# G850V_ESP8266_II_v6.net
KiCad netlist of a schematic drawn in EAGLE
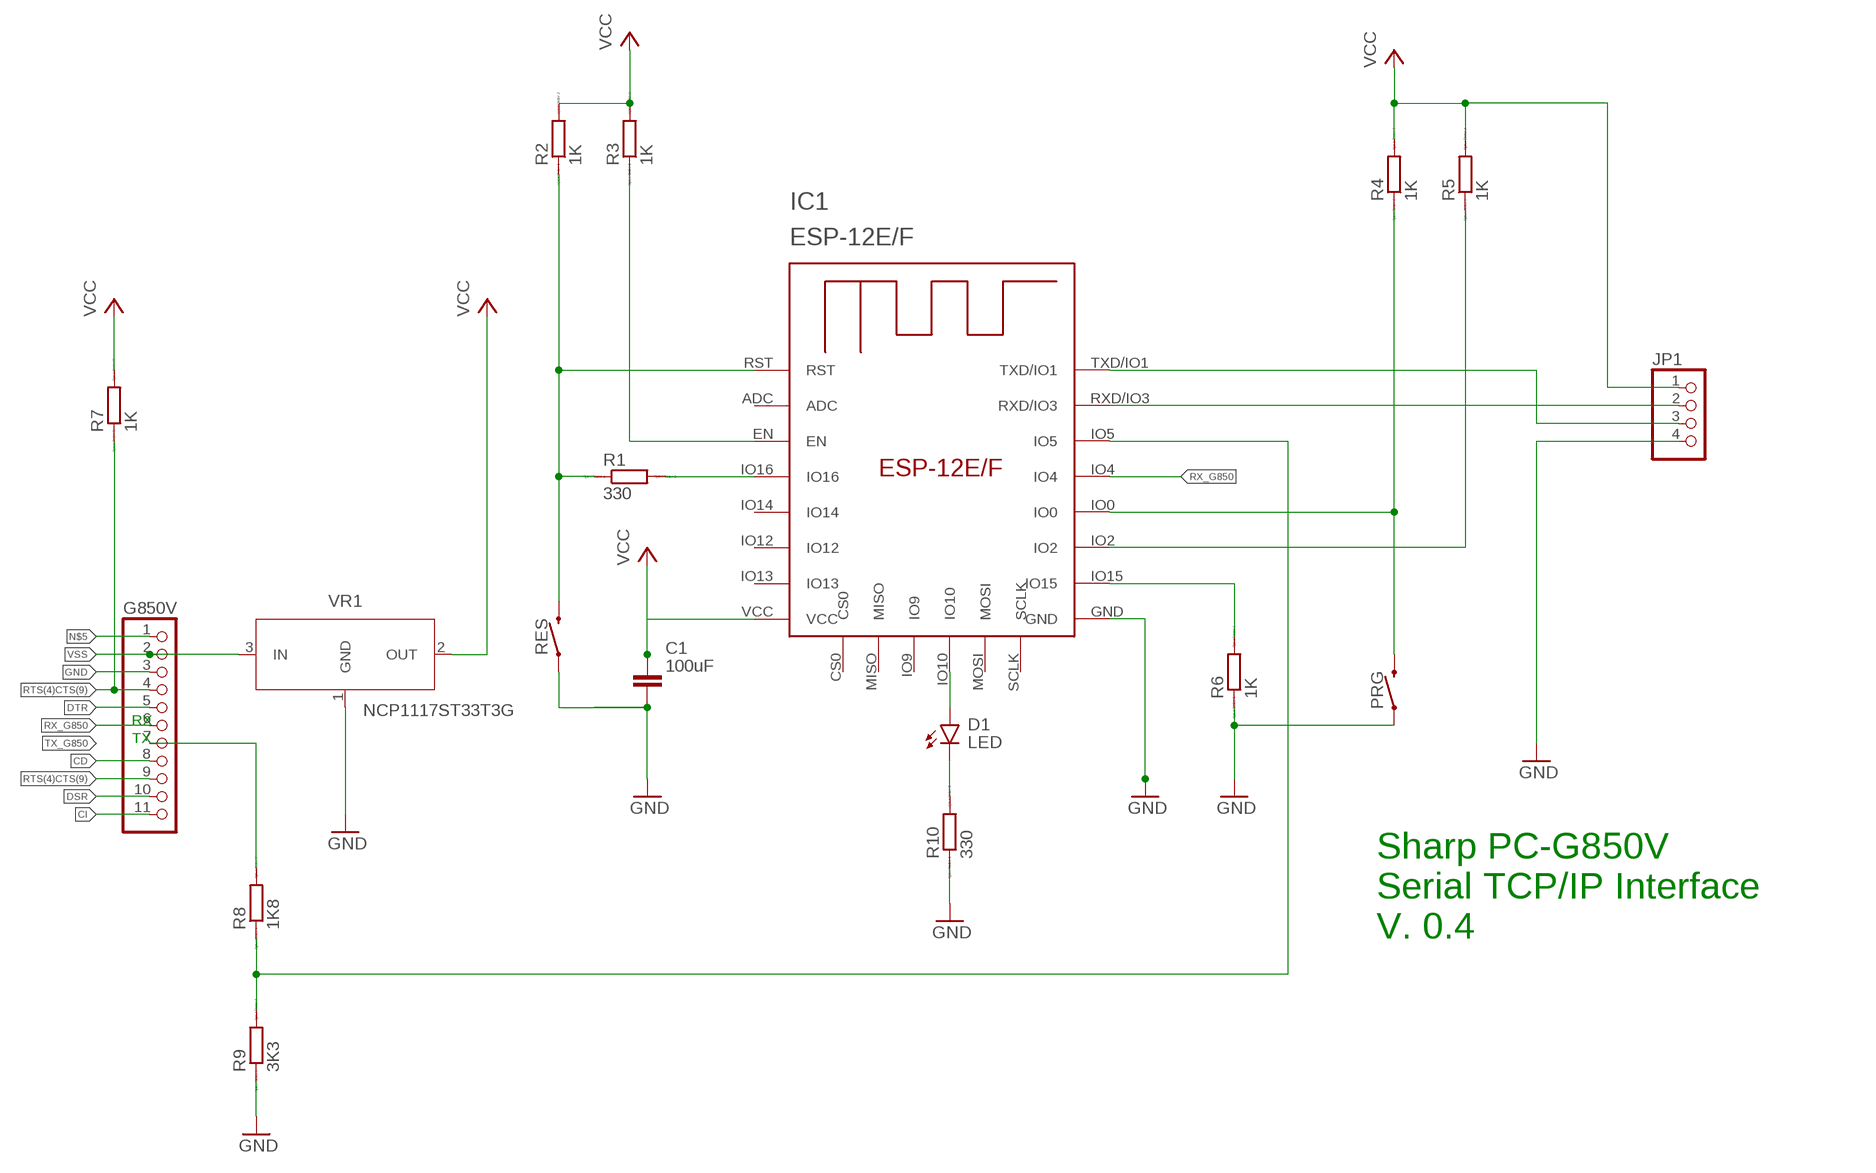
[diagram p0: schematic, sheet 1]

(export (version "E")
  (design (tool "Eeschema 10.0.6"))
  (components
    (comp (ref "C1")
      (value "100uF")
      (footprint "eagle-import:CAPC4532X135")
      (libsource (lib "eagle-import") (part "CCHIP-1812(4532-METRIC)_"))
    )
    (comp (ref "D1")
      (value "LED")
      (footprint "eagle-import:LEDC2012X110N_FLAT-B")
      (libsource (lib "eagle-import") (part "CHIP-FLAT-B_0805"))
    )
    (comp (ref "G850V")
      (value "PINHD-1X11/90")
      (footprint "eagle-import:1X11_90")
      (libsource (lib "eagle-import") (part "PINHD-1X11/90"))
    )
    (comp (ref "IC1")
      (value "ESP-12E/F")
      (footprint "eagle-import:ESP-12E")
      (libsource (lib "eagle-import") (part "ESP-12E/F"))
    )
    (comp (ref "JP1")
      (value "PINHD-1X4/90")
      (footprint "eagle-import:1X04_90")
      (libsource (lib "eagle-import") (part "PINHD-1X4/90"))
    )
    (comp (ref "PRG")
      (value "MOMENTARY-SWITCH-SPST-SMD-4.6X2.8MM")
      (footprint "eagle-import:TACTILE_SWITCH_SMD_4.6X2.8MM")
      (libsource (lib "eagle-import") (part "MOMENTARY-SWITCH-SPST-SMD-4.6X2.8MM"))
    )
    (comp (ref "R1")
      (value "330")
      (footprint "eagle-import:R0805")
      (libsource (lib "eagle-import") (part "R"))
    )
    (comp (ref "R2")
      (value "1K")
      (footprint "eagle-import:R0805")
      (libsource (lib "eagle-import") (part "R"))
    )
    (comp (ref "R3")
      (value "1K")
      (footprint "eagle-import:R0805")
      (libsource (lib "eagle-import") (part "R"))
    )
    (comp (ref "R4")
      (value "1K")
      (footprint "eagle-import:R0805")
      (libsource (lib "eagle-import") (part "R"))
    )
    (comp (ref "R5")
      (value "1K")
      (footprint "eagle-import:R0805")
      (libsource (lib "eagle-import") (part "R"))
    )
    (comp (ref "R6")
      (value "1K")
      (footprint "eagle-import:R0805")
      (libsource (lib "eagle-import") (part "R"))
    )
    (comp (ref "R7")
      (value "1K")
      (footprint "eagle-import:R0805")
      (libsource (lib "eagle-import") (part "R"))
    )
    (comp (ref "R8")
      (value "1K8")
      (footprint "eagle-import:R0805")
      (libsource (lib "eagle-import") (part "R"))
    )
    (comp (ref "R9")
      (value "3K3")
      (footprint "eagle-import:R0805")
      (libsource (lib "eagle-import") (part "R"))
    )
    (comp (ref "R10")
      (value "330")
      (footprint "eagle-import:R0805")
      (libsource (lib "eagle-import") (part "R"))
    )
    (comp (ref "RES")
      (value "MOMENTARY-SWITCH-SPST-SMD-4.6X2.8MM")
      (footprint "eagle-import:TACTILE_SWITCH_SMD_4.6X2.8MM")
      (libsource (lib "eagle-import") (part "MOMENTARY-SWITCH-SPST-SMD-4.6X2.8MM"))
    )
    (comp (ref "VR1")
      (value "NCP1117ST33T3G")
      (footprint "eagle-import:SOT230P700X170-4")
      (fields (field (name "MANUFACTURER") "ON Semiconductor"))
      (libsource (lib "eagle-import") (part "NCP1117ST33T3GSOT-223"))
    )
  )
  (nets
    (net (code "1") (name "CD") (class "Default")
      (node (ref "G850V") (pin "8") (pinfunction "8_8") (pintype "passive"))
    )
    (net (code "2") (name "CI") (class "Default")
      (node (ref "G850V") (pin "11") (pinfunction "11_11") (pintype "passive"))
    )
    (net (code "3") (name "DSR") (class "Default")
      (node (ref "G850V") (pin "10") (pinfunction "10_10") (pintype "passive"))
    )
    (net (code "4") (name "DTR") (class "Default")
      (node (ref "G850V") (pin "5") (pinfunction "5_5") (pintype "passive"))
    )
    (net (code "5") (name "GND") (class "Default")
      (node (ref "C1") (pin "2") (pinfunction "2_2") (pintype "passive"))
      (node (ref "G850V") (pin "3") (pinfunction "3_3") (pintype "passive"))
      (node (ref "IC1") (pin "GND") (pinfunction "GND_GND") (pintype "power_in"))
      (node (ref "JP1") (pin "4") (pinfunction "4_4") (pintype "passive"))
      (node (ref "PRG") (pin "1") (pinfunction "1_1") (pintype "passive"))
      (node (ref "PRG") (pin "2") (pinfunction "1_2") (pintype "passive"))
      (node (ref "R10") (pin "1") (pinfunction "1_1") (pintype "passive"))
      (node (ref "R6") (pin "1") (pinfunction "1_1") (pintype "passive"))
      (node (ref "R9") (pin "1") (pinfunction "1_1") (pintype "passive"))
      (node (ref "RES") (pin "1") (pinfunction "1_1") (pintype "passive"))
      (node (ref "RES") (pin "2") (pinfunction "1_2") (pintype "passive"))
      (node (ref "VR1") (pin "1") (pinfunction "GND_1") (pintype "passive"))
    )
    (net (code "6") (name "N$5") (class "Default")
      (node (ref "G850V") (pin "1") (pinfunction "1_1") (pintype "passive"))
    )
    (net (code "7") (name "Net-(D1-PadA)") (class "Default")
      (node (ref "D1") (pin "A") (pinfunction "A_A") (pintype "passive"))
      (node (ref "IC1") (pin "IO10") (pinfunction "IO10_IO10") (pintype "bidirectional"))
    )
    (net (code "8") (name "Net-(D1-PadC)") (class "Default")
      (node (ref "D1") (pin "C") (pinfunction "C_C") (pintype "passive"))
      (node (ref "R10") (pin "2") (pinfunction "2_2") (pintype "passive"))
    )
    (net (code "9") (name "Net-(IC1-PadEN)") (class "Default")
      (node (ref "IC1") (pin "EN") (pinfunction "EN_EN") (pintype "bidirectional"))
      (node (ref "R3") (pin "1") (pinfunction "1_1") (pintype "passive"))
    )
    (net (code "10") (name "Net-(IC1-PadIO0)") (class "Default")
      (node (ref "IC1") (pin "IO0") (pinfunction "IO0_IO0") (pintype "bidirectional"))
      (node (ref "PRG") (pin "3") (pinfunction "2_3") (pintype "passive"))
      (node (ref "PRG") (pin "4") (pinfunction "2_4") (pintype "passive"))
      (node (ref "R4") (pin "1") (pinfunction "1_1") (pintype "passive"))
    )
    (net (code "11") (name "Net-(IC1-PadIO2)") (class "Default")
      (node (ref "IC1") (pin "IO2") (pinfunction "IO2_IO2") (pintype "bidirectional"))
      (node (ref "R5") (pin "1") (pinfunction "1_1") (pintype "passive"))
    )
    (net (code "12") (name "Net-(IC1-PadIO5)") (class "Default")
      (node (ref "IC1") (pin "IO5") (pinfunction "IO5_IO5") (pintype "bidirectional"))
      (node (ref "R8") (pin "1") (pinfunction "1_1") (pintype "passive"))
      (node (ref "R9") (pin "2") (pinfunction "2_2") (pintype "passive"))
    )
    (net (code "13") (name "Net-(IC1-PadIO15)") (class "Default")
      (node (ref "IC1") (pin "IO15") (pinfunction "IO15_IO15") (pintype "bidirectional"))
      (node (ref "R6") (pin "2") (pinfunction "2_2") (pintype "passive"))
    )
    (net (code "14") (name "Net-(IC1-PadIO16)") (class "Default")
      (node (ref "IC1") (pin "IO16") (pinfunction "IO16_IO16") (pintype "bidirectional"))
      (node (ref "R1") (pin "2") (pinfunction "2_2") (pintype "passive"))
    )
    (net (code "15") (name "Net-(IC1-PadRST)") (class "Default")
      (node (ref "IC1") (pin "RST") (pinfunction "RST_RST") (pintype "input"))
      (node (ref "R1") (pin "1") (pinfunction "1_1") (pintype "passive"))
      (node (ref "R2") (pin "1") (pinfunction "1_1") (pintype "passive"))
      (node (ref "RES") (pin "3") (pinfunction "2_3") (pintype "passive"))
      (node (ref "RES") (pin "4") (pinfunction "2_4") (pintype "passive"))
    )
    (net (code "16") (name "Net-(IC1-PadRXD{slash}IO3)") (class "Default")
      (node (ref "IC1") (pin "RXD/IO3") (pinfunction "RXD/IO3_RXD/IO3") (pintype "bidirectional"))
      (node (ref "JP1") (pin "2") (pinfunction "2_2") (pintype "passive"))
    )
    (net (code "17") (name "Net-(IC1-PadTXD{slash}IO1)") (class "Default")
      (node (ref "IC1") (pin "TXD/IO1") (pinfunction "TXD/IO1_TXD/IO1") (pintype "bidirectional"))
      (node (ref "JP1") (pin "3") (pinfunction "3_3") (pintype "passive"))
    )
    (net (code "18") (name "RTS(4)CTS(9)") (class "Default")
      (node (ref "G850V") (pin "4") (pinfunction "4_4") (pintype "passive"))
      (node (ref "G850V") (pin "9") (pinfunction "9_9") (pintype "passive"))
      (node (ref "R7") (pin "1") (pinfunction "1_1") (pintype "passive"))
    )
    (net (code "19") (name "RX_G850") (class "Default")
      (node (ref "G850V") (pin "6") (pinfunction "6_6") (pintype "passive"))
      (node (ref "IC1") (pin "IO4") (pinfunction "IO4_IO4") (pintype "bidirectional"))
    )
    (net (code "20") (name "TX_G850") (class "Default")
      (node (ref "G850V") (pin "7") (pinfunction "7_7") (pintype "passive"))
      (node (ref "R8") (pin "2") (pinfunction "2_2") (pintype "passive"))
    )
    (net (code "21") (name "VCC") (class "Default")
      (node (ref "C1") (pin "1") (pinfunction "1_1") (pintype "passive"))
      (node (ref "IC1") (pin "VCC") (pinfunction "VCC_VCC") (pintype "power_in"))
      (node (ref "JP1") (pin "1") (pinfunction "1_1") (pintype "passive"))
      (node (ref "R2") (pin "2") (pinfunction "2_2") (pintype "passive"))
      (node (ref "R3") (pin "2") (pinfunction "2_2") (pintype "passive"))
      (node (ref "R4") (pin "2") (pinfunction "2_2") (pintype "passive"))
      (node (ref "R5") (pin "2") (pinfunction "2_2") (pintype "passive"))
      (node (ref "R7") (pin "2") (pinfunction "2_2") (pintype "passive"))
      (node (ref "VR1") (pin "2") (pinfunction "OUT_2") (pintype "output"))
    )
    (net (code "22") (name "VSS") (class "Default")
      (node (ref "G850V") (pin "2") (pinfunction "2_2") (pintype "passive"))
      (node (ref "VR1") (pin "3") (pinfunction "IN_3") (pintype "input"))
    )
    (net (code "23") (name "unconnected-(IC1-PadADC)") (class "Default")
      (node (ref "IC1") (pin "ADC") (pinfunction "ADC_ADC") (pintype "bidirectional"))
    )
    (net (code "24") (name "unconnected-(IC1-PadCS0)") (class "Default")
      (node (ref "IC1") (pin "CS0") (pinfunction "CS0_CS0") (pintype "bidirectional"))
    )
    (net (code "25") (name "unconnected-(IC1-PadIO9)") (class "Default")
      (node (ref "IC1") (pin "IO9") (pinfunction "IO9_IO9") (pintype "bidirectional"))
    )
    (net (code "26") (name "unconnected-(IC1-PadIO12)") (class "Default")
      (node (ref "IC1") (pin "IO12") (pinfunction "IO12_IO12") (pintype "bidirectional"))
    )
    (net (code "27") (name "unconnected-(IC1-PadIO13)") (class "Default")
      (node (ref "IC1") (pin "IO13") (pinfunction "IO13_IO13") (pintype "bidirectional"))
    )
    (net (code "28") (name "unconnected-(IC1-PadIO14)") (class "Default")
      (node (ref "IC1") (pin "IO14") (pinfunction "IO14_IO14") (pintype "bidirectional"))
    )
    (net (code "29") (name "unconnected-(IC1-PadMISO)") (class "Default")
      (node (ref "IC1") (pin "MISO") (pinfunction "MISO_MISO") (pintype "bidirectional"))
    )
    (net (code "30") (name "unconnected-(IC1-PadMOSI)") (class "Default")
      (node (ref "IC1") (pin "MOSI") (pinfunction "MOSI_MOSI") (pintype "bidirectional"))
    )
    (net (code "31") (name "unconnected-(IC1-PadSCLK)") (class "Default")
      (node (ref "IC1") (pin "SCLK") (pinfunction "SCLK_SCLK") (pintype "bidirectional"))
    )
  )
)
